# IMU.net
KiCad netlist of a schematic drawn in Altium Designer
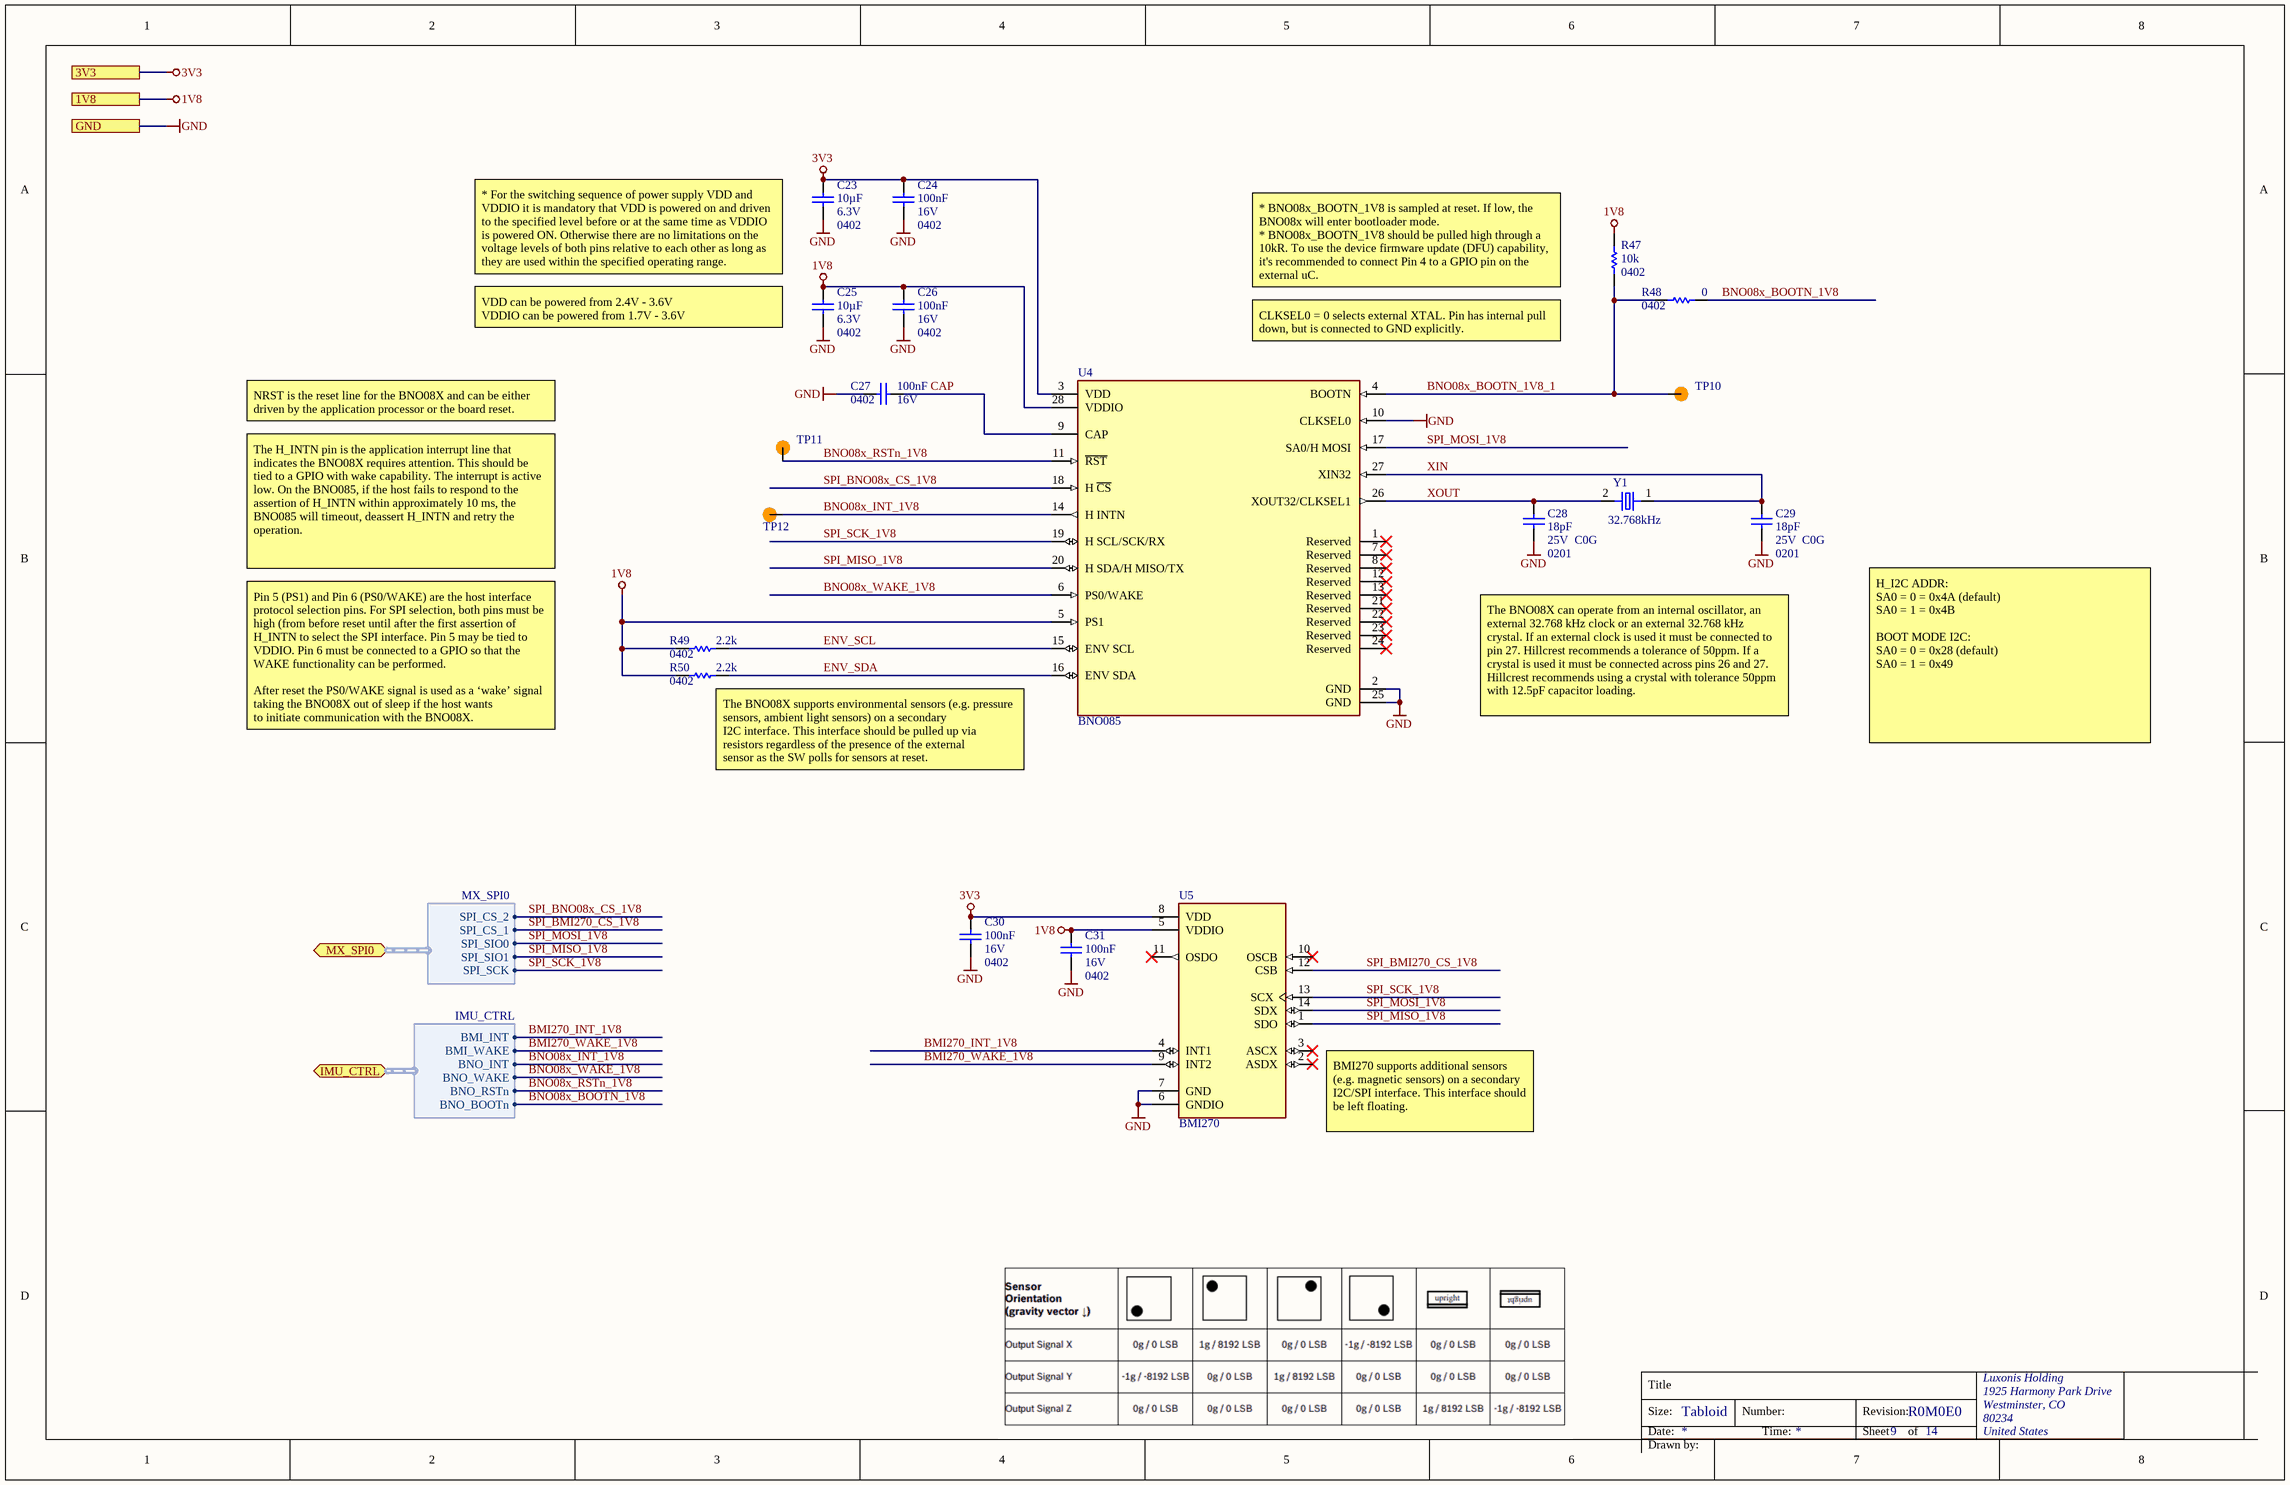
[diagram p0: IMU.SchDoc]

(export (version "E")
  (design (tool "Eeschema 10.0.6"))
  (components
    (comp (ref "C23")
      (value "10µF")
      (footprint "CAPC0402(1005)70_N")
      (description "CAP CER 10UF 6.3V X5R 0402 20%")
      (fields
        (field (name "VOLTAGE RATING") "6.3V")
        (field (name "CASE/PACKAGE") "0402")
        (field (name "TOLERANCE") "20%")
        (field (name "Comment") "GRM155R60J106ME15D")
      )
      (libsource (lib "Luxonis LLC") (part "LLL153C70G474ME17E"))
    )
    (comp (ref "C24")
      (value "100nF")
      (footprint "CAPC0402(1005)60_N")
      (description "CAP CER 0.1UF 16V X7R 0402 10%")
      (fields
        (field (name "VOLTAGE RATING") "16V")
        (field (name "CASE/PACKAGE") "0402")
        (field (name "TOLERANCE") "10%")
        (field (name "Comment") "CL05B104KO5NFNC")
      )
      (libsource (lib "Luxonis LLC") (part "GRM188R61C475KAAJD"))
    )
    (comp (ref "C25")
      (value "10µF")
      (footprint "CAPC0402(1005)70_N")
      (description "CAP CER 10UF 6.3V X5R 0402 20%")
      (fields
        (field (name "VOLTAGE RATING") "6.3V")
        (field (name "CASE/PACKAGE") "0402")
        (field (name "TOLERANCE") "20%")
        (field (name "Comment") "GRM155R60J106ME15D")
      )
      (libsource (lib "Luxonis LLC") (part "LLL153C70G474ME17E"))
    )
    (comp (ref "C26")
      (value "100nF")
      (footprint "CAPC0402(1005)60_N")
      (description "CAP CER 0.1UF 16V X7R 0402 10%")
      (fields
        (field (name "VOLTAGE RATING") "16V")
        (field (name "CASE/PACKAGE") "0402")
        (field (name "TOLERANCE") "10%")
        (field (name "Comment") "CL05B104KO5NFNC")
      )
      (libsource (lib "Luxonis LLC") (part "GRM188R61C475KAAJD"))
    )
    (comp (ref "C27")
      (value "100nF")
      (footprint "CAPC0402(1005)60_N")
      (description "CAP CER 0.1UF 16V X7R 0402 10%")
      (fields
        (field (name "VOLTAGE RATING") "16V")
        (field (name "CASE/PACKAGE") "0402")
        (field (name "TOLERANCE") "10%")
        (field (name "Comment") "CL05B104KO5NFNC")
      )
      (libsource (lib "Luxonis LLC") (part "GRM188R61C475KAAJD"))
    )
    (comp (ref "C28")
      (value "18pF")
      (footprint "CAPC0201(0603)33_L")
      (description "CAP CER 18PF 25V C0G 0201 10%")
      (fields
        (field (name "CASE/PACKAGE") "0201")
        (field (name "TOLERANCE") "1%")
        (field (name "VOLTAGE RATING") "25V")
        (field (name "DIELECTRIC") "C0G")
        (field (name "Comment") "GRM0335C1E180FA01D")
      )
      (libsource (lib "Luxonis LLC") (part "LLL153C70G474ME17E"))
    )
    (comp (ref "C29")
      (value "18pF")
      (footprint "CAPC0201(0603)33_L")
      (description "CAP CER 18PF 25V C0G 0201 10%")
      (fields
        (field (name "CASE/PACKAGE") "0201")
        (field (name "TOLERANCE") "1%")
        (field (name "VOLTAGE RATING") "25V")
        (field (name "DIELECTRIC") "C0G")
        (field (name "Comment") "GRM0335C1E180FA01D")
      )
      (libsource (lib "Luxonis LLC") (part "LLL153C70G474ME17E"))
    )
    (comp (ref "C30")
      (value "100nF")
      (footprint "CAPC0402(1005)60_N")
      (description "CAP CER 0.1UF 16V X7R 0402 10%")
      (fields
        (field (name "VOLTAGE RATING") "16V")
        (field (name "CASE/PACKAGE") "0402")
        (field (name "TOLERANCE") "10%")
        (field (name "Comment") "CL05B104KO5NFNC")
      )
      (libsource (lib "Luxonis LLC") (part "GRM188R61C475KAAJD"))
    )
    (comp (ref "C31")
      (value "100nF")
      (footprint "CAPC0402(1005)60_N")
      (description "CAP CER 0.1UF 16V X7R 0402 10%")
      (fields
        (field (name "VOLTAGE RATING") "16V")
        (field (name "CASE/PACKAGE") "0402")
        (field (name "TOLERANCE") "10%")
        (field (name "Comment") "CL05B104KO5NFNC")
      )
      (libsource (lib "Luxonis LLC") (part "GRM188R61C475KAAJD"))
    )
    (comp (ref "R47")
      (value "10k")
      (footprint "RESC0402(1005)_N")
      (description "RES SMD 10K OHM 1% 1/16W 0402")
      (fields
        (field (name "CASE/PACKAGE") "0402")
        (field (name "TOLERANCE") "1%")
        (field (name "Comment") "RC0402FR-1310KL")
      )
      (libsource (lib "Luxonis LLC") (part "RC0402FR-0722RL_1"))
    )
    (comp (ref "R48")
      (value "0")
      (footprint "RESC0402(1005)_L")
      (description "RES SMD 0 OHM 5% 1/16W 0402")
      (fields
        (field (name "CASE/PACKAGE") "0402")
        (field (name "TOLERANCE") "5%")
        (field (name "Comment") "CRCW04020000Z0ED")
      )
      (libsource (lib "Luxonis LLC") (part "Default resistor symbol"))
    )
    (comp (ref "R49")
      (value "2.2k")
      (footprint "RESC0402(1005)_L")
      (description "RES SMD 2.2K OHM 1% 1/16W 0402")
      (fields
        (field (name "CASE/PACKAGE") "0402")
        (field (name "TOLERANCE") "1%")
        (field (name "Comment") "RC0402FR-072K2L")
      )
      (libsource (lib "Luxonis LLC") (part "Default resistor symbol"))
    )
    (comp (ref "R50")
      (value "2.2k")
      (footprint "RESC0402(1005)_L")
      (description "RES SMD 2.2K OHM 1% 1/16W 0402")
      (fields
        (field (name "CASE/PACKAGE") "0402")
        (field (name "TOLERANCE") "1%")
        (field (name "Comment") "RC0402FR-072K2L")
      )
      (libsource (lib "Luxonis LLC") (part "Default resistor symbol"))
    )
    (comp (ref "TP10")
      (value "TEST_POINT")
      (footprint "TP075_150_NS")
      (libsource (lib "Luxonis LLC") (part "TEST_POINT"))
    )
    (comp (ref "TP11")
      (value "TEST_POINT")
      (footprint "TP075_150_NS")
      (libsource (lib "Luxonis LLC") (part "TEST_POINT"))
    )
    (comp (ref "TP12")
      (value "TEST_POINT")
      (footprint "TP075_150_NS")
      (libsource (lib "Luxonis LLC") (part "TEST_POINT"))
    )
    (comp (ref "U4")
      (value "BNO085")
      (footprint "BNO085")
      (description "IMU ACCEL/GYRO/MAG I2C 32BIT")
      (libsource (lib "Luxonis LLC") (part "BNO085"))
    )
    (comp (ref "U5")
      (value "BMI270")
      (footprint "XDCR_BMI270")
      (description "Accelerometer, Gyroscope, 6 Axis Sensor IÂ²C, SPI Output")
      (libsource (lib "LuxonisMaster") (part "BMI270"))
    )
    (comp (ref "Y1")
      (value "ABS06-127-32.768KHZ-T")
      (footprint "ABS06-127-32.768KHZ-T")
      (description "CRYSTAL 32.768kHz ±20ppm Crystal 12.5pF 90 kOhms 2-SMD, No Lead")
      (fields (field (name "FREQUENCY") "32.768kHz") (field (name "TOLERANCE") "20ppm"))
      (libsource (lib "Luxonis LLC") (part "ABS06-127-32.768KHZ-T"))
    )
  )
  (nets
    (net (code "3") (name "/BMI270_INT_1V8") (class "Default")
      (node (ref "U5") (pin "4") (pinfunction "INT1_4") (pintype "bidirectional"))
    )
    (net (code "4") (name "/BMI270_WAKE_1V8") (class "Default")
      (node (ref "U5") (pin "9") (pinfunction "INT2_9") (pintype "bidirectional"))
    )
    (net (code "5") (name "/BNO08x_BOOTN_1V8") (class "Default")
      (node (ref "R48") (pin "2") (pinfunction "2_2") (pintype "passive"))
    )
    (net (code "6") (name "/BNO08x_BOOTN_1V8_1") (class "Default")
      (node (ref "R47") (pin "1") (pinfunction "1_1") (pintype "passive"))
      (node (ref "R48") (pin "1") (pinfunction "1_1") (pintype "passive"))
      (node (ref "TP10") (pin "1") (pintype "passive"))
      (node (ref "U4") (pin "4") (pinfunction "BOOTN_4") (pintype "input"))
    )
    (net (code "7") (name "/BNO08x_INT_1V8") (class "Default")
      (node (ref "TP12") (pin "1") (pintype "passive"))
      (node (ref "U4") (pin "14") (pinfunction "H_INTN_14") (pintype "output"))
    )
    (net (code "8") (name "/BNO08x_RSTn_1V8") (class "Default")
      (node (ref "TP11") (pin "1") (pintype "passive"))
      (node (ref "U4") (pin "11") (pinfunction "~{RST}_11") (pintype "input"))
    )
    (net (code "9") (name "/BNO08x_WAKE_1V8") (class "Default")
      (node (ref "U4") (pin "6") (pinfunction "PS0/WAKE_6") (pintype "input"))
    )
    (net (code "10") (name "/CAP") (class "Default")
      (node (ref "C27") (pin "1") (pinfunction "1_1") (pintype "passive"))
      (node (ref "U4") (pin "9") (pinfunction "CAP_9") (pintype "passive"))
    )
    (net (code "11") (name "/ENV_SCL") (class "Default")
      (node (ref "R49") (pin "2") (pinfunction "2_2") (pintype "passive"))
      (node (ref "U4") (pin "15") (pinfunction "ENV_SCL_15") (pintype "bidirectional"))
    )
    (net (code "12") (name "/ENV_SDA") (class "Default")
      (node (ref "R50") (pin "2") (pinfunction "2_2") (pintype "passive"))
      (node (ref "U4") (pin "16") (pinfunction "ENV_SDA_16") (pintype "bidirectional"))
    )
    (net (code "13") (name "/SPI_BMI270_CS_1V8") (class "Default")
      (node (ref "U5") (pin "12") (pinfunction "CSB_12") (pintype "input"))
    )
    (net (code "14") (name "/SPI_BNO08x_CS_1V8") (class "Default")
      (node (ref "U4") (pin "18") (pinfunction "H_~{CS}_18") (pintype "input"))
    )
    (net (code "15") (name "/SPI_MISO_1V8") (class "Default")
      (node (ref "U4") (pin "20") (pinfunction "H_SDA/H_MISO/TX_20") (pintype "bidirectional"))
      (node (ref "U5") (pin "1") (pinfunction "SDO_1") (pintype "bidirectional"))
    )
    (net (code "16") (name "/SPI_MOSI_1V8") (class "Default")
      (node (ref "U4") (pin "17") (pinfunction "SA0/H_MOSI_17") (pintype "input"))
      (node (ref "U5") (pin "14") (pinfunction "SDX_14") (pintype "bidirectional"))
    )
    (net (code "17") (name "/SPI_SCK_1V8") (class "Default")
      (node (ref "U4") (pin "19") (pinfunction "H_SCL/SCK/RX_19") (pintype "bidirectional"))
      (node (ref "U5") (pin "13") (pinfunction "SCX_13") (pintype "input"))
    )
    (net (code "18") (name "/XIN") (class "Default")
      (node (ref "C29") (pin "2") (pinfunction "2_2") (pintype "passive"))
      (node (ref "U4") (pin "27") (pinfunction "XIN32_27") (pintype "input"))
      (node (ref "Y1") (pin "1") (pinfunction "1_1") (pintype "passive"))
    )
    (net (code "19") (name "/XOUT") (class "Default")
      (node (ref "C28") (pin "2") (pinfunction "2_2") (pintype "passive"))
      (node (ref "U4") (pin "26") (pinfunction "XOUT32/CLKSEL1_26") (pintype "output"))
      (node (ref "Y1") (pin "2") (pinfunction "2_2") (pintype "passive"))
    )
    (net (code "22") (name "1V8") (class "Default")
      (node (ref "C25") (pin "2") (pinfunction "2_2") (pintype "passive"))
      (node (ref "C26") (pin "2") (pinfunction "2_2") (pintype "passive"))
      (node (ref "C31") (pin "2") (pinfunction "2_2") (pintype "passive"))
      (node (ref "R47") (pin "2") (pinfunction "2_2") (pintype "passive"))
      (node (ref "R49") (pin "1") (pinfunction "1_1") (pintype "passive"))
      (node (ref "R50") (pin "1") (pinfunction "1_1") (pintype "passive"))
      (node (ref "U4") (pin "28") (pinfunction "VDDIO_28") (pintype "power_in"))
      (node (ref "U4") (pin "5") (pinfunction "PS1_5") (pintype "input"))
      (node (ref "U5") (pin "5") (pinfunction "VDDIO_5") (pintype "power_in"))
    )
    (net (code "23") (name "3V3") (class "Default")
      (node (ref "C23") (pin "2") (pinfunction "2_2") (pintype "passive"))
      (node (ref "C24") (pin "2") (pinfunction "2_2") (pintype "passive"))
      (node (ref "C30") (pin "2") (pinfunction "2_2") (pintype "passive"))
      (node (ref "U4") (pin "3") (pinfunction "VDD_3") (pintype "power_in"))
      (node (ref "U5") (pin "8") (pinfunction "VDD_8") (pintype "power_in"))
    )
    (net (code "24") (name "GND") (class "Default")
      (node (ref "C23") (pin "1") (pinfunction "1_1") (pintype "passive"))
      (node (ref "C24") (pin "1") (pinfunction "1_1") (pintype "passive"))
      (node (ref "C25") (pin "1") (pinfunction "1_1") (pintype "passive"))
      (node (ref "C26") (pin "1") (pinfunction "1_1") (pintype "passive"))
      (node (ref "C27") (pin "2") (pinfunction "2_2") (pintype "passive"))
      (node (ref "C28") (pin "1") (pinfunction "1_1") (pintype "passive"))
      (node (ref "C29") (pin "1") (pinfunction "1_1") (pintype "passive"))
      (node (ref "C30") (pin "1") (pinfunction "1_1") (pintype "passive"))
      (node (ref "C31") (pin "1") (pinfunction "1_1") (pintype "passive"))
      (node (ref "U4") (pin "10") (pinfunction "CLKSEL0_10") (pintype "input"))
      (node (ref "U4") (pin "2") (pinfunction "GND_2") (pintype "power_in"))
      (node (ref "U4") (pin "25") (pinfunction "GND_25") (pintype "power_in"))
      (node (ref "U5") (pin "6") (pinfunction "GNDIO_6") (pintype "power_in"))
      (node (ref "U5") (pin "7") (pinfunction "GND_7") (pintype "power_in"))
    )
    (net (code "25") (name "unconnected-(U4-Reserved-Pad1)") (class "Default")
      (node (ref "U4") (pin "1") (pinfunction "Reserved_1") (pintype "passive+no_connect"))
    )
    (net (code "26") (name "unconnected-(U4-Reserved-Pad7)") (class "Default")
      (node (ref "U4") (pin "7") (pinfunction "Reserved_7") (pintype "passive+no_connect"))
    )
    (net (code "27") (name "unconnected-(U4-Reserved-Pad8)") (class "Default")
      (node (ref "U4") (pin "8") (pinfunction "Reserved_8") (pintype "passive+no_connect"))
    )
    (net (code "28") (name "unconnected-(U4-Reserved-Pad12)") (class "Default")
      (node (ref "U4") (pin "12") (pinfunction "Reserved_12") (pintype "passive+no_connect"))
    )
    (net (code "29") (name "unconnected-(U4-Reserved-Pad13)") (class "Default")
      (node (ref "U4") (pin "13") (pinfunction "Reserved_13") (pintype "passive+no_connect"))
    )
    (net (code "30") (name "unconnected-(U4-Reserved-Pad21)") (class "Default")
      (node (ref "U4") (pin "21") (pinfunction "Reserved_21") (pintype "passive+no_connect"))
    )
    (net (code "31") (name "unconnected-(U4-Reserved-Pad22)") (class "Default")
      (node (ref "U4") (pin "22") (pinfunction "Reserved_22") (pintype "passive+no_connect"))
    )
    (net (code "32") (name "unconnected-(U4-Reserved-Pad23)") (class "Default")
      (node (ref "U4") (pin "23") (pinfunction "Reserved_23") (pintype "passive+no_connect"))
    )
    (net (code "33") (name "unconnected-(U4-Reserved-Pad24)") (class "Default")
      (node (ref "U4") (pin "24") (pinfunction "Reserved_24") (pintype "passive+no_connect"))
    )
    (net (code "34") (name "unconnected-(U5-ASCX-Pad3)") (class "Default")
      (node (ref "U5") (pin "3") (pinfunction "ASCX_3") (pintype "bidirectional+no_connect"))
    )
    (net (code "35") (name "unconnected-(U5-ASDX-Pad2)") (class "Default")
      (node (ref "U5") (pin "2") (pinfunction "ASDX_2") (pintype "bidirectional+no_connect"))
    )
    (net (code "36") (name "unconnected-(U5-OSCB-Pad10)") (class "Default")
      (node (ref "U5") (pin "10") (pinfunction "OSCB_10") (pintype "input+no_connect"))
    )
    (net (code "37") (name "unconnected-(U5-OSDO-Pad11)") (class "Default")
      (node (ref "U5") (pin "11") (pinfunction "OSDO_11") (pintype "output+no_connect"))
    )
  )
)
